# Remote_Linear_Actuator.net
KiCad netlist of a schematic drawn in Altium Designer
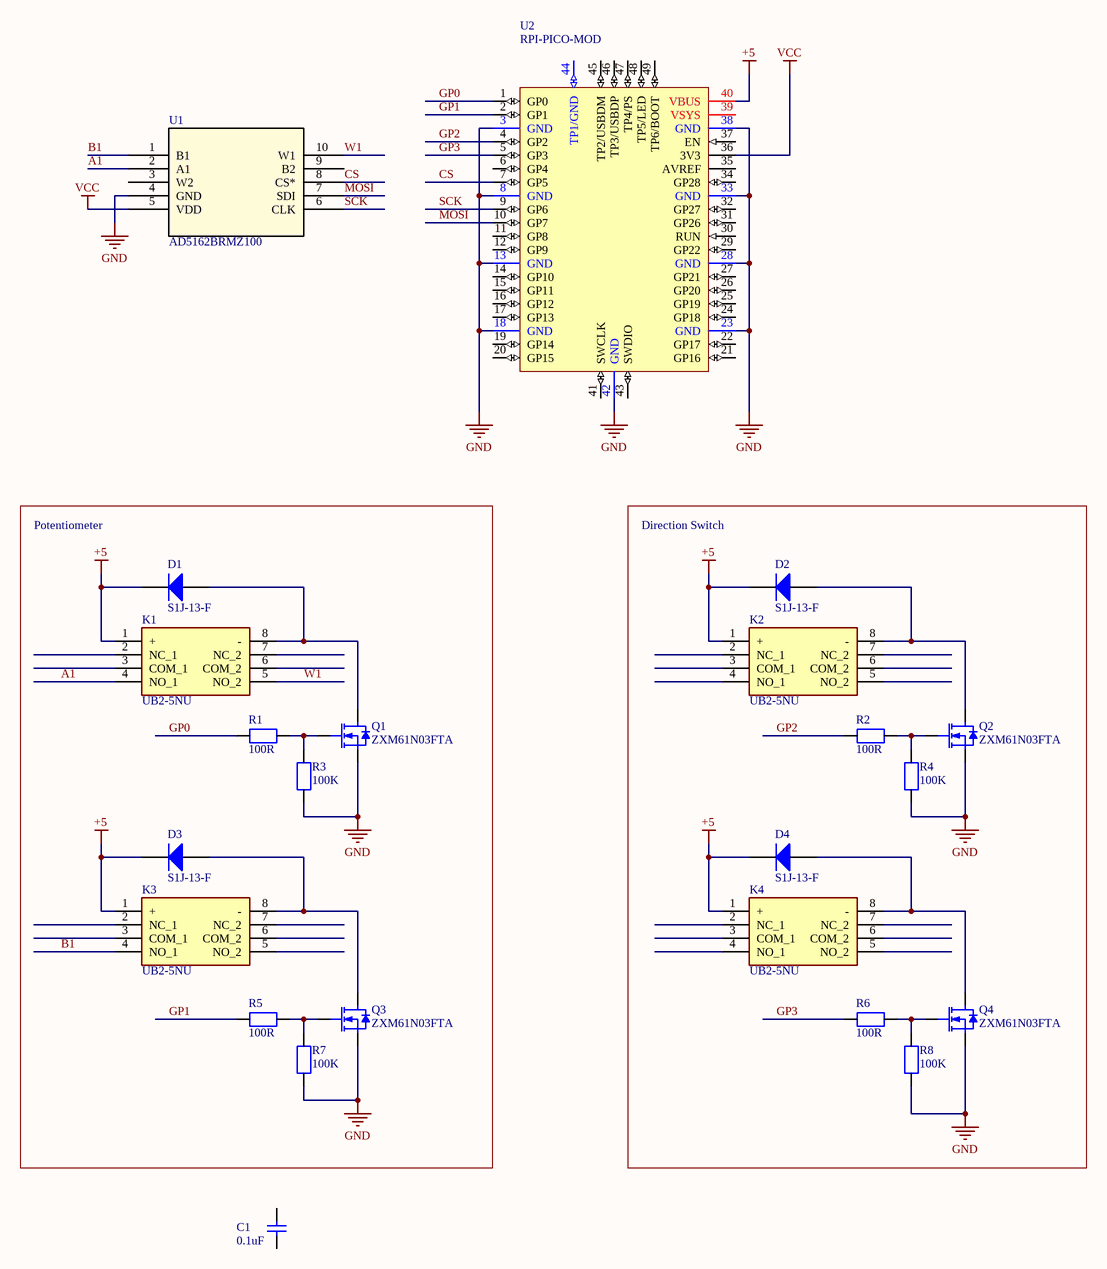
[diagram p0: Remote Linear Actuator.SchDoc]

(export (version "E")
  (design (tool "Eeschema 10.0.6"))
  (components
    (comp (ref "C1")
      (value "0.1uF")
      (footprint "0603X90")
      (description "0.1uf, 50V,0603")
      (fields (field (name "MANUFACTURER") "Yageo") (field (name "MANUFACTURERPART") "CC0603KRX7R9BB104"))
      (libsource (lib "CUSTOMSCH") (part "CAP"))
    )
    (comp (ref "D1")
      (value "S1J-13-F")
      (footprint "DIOM-430X270X245")
      (description "DIODE GEN PURP 600V 1A SMA")
      (fields (field (name "MANUFACTURER") "Diodes Incorporated"))
      (libsource (lib "CUSTOMSCH") (part "Diode"))
    )
    (comp (ref "D2")
      (value "S1J-13-F")
      (footprint "DIOM-430X270X245")
      (description "DIODE GEN PURP 600V 1A SMA")
      (fields (field (name "MANUFACTURER") "Diodes Incorporated"))
      (libsource (lib "CUSTOMSCH") (part "Diode"))
    )
    (comp (ref "D3")
      (value "S1J-13-F")
      (footprint "DIOM-430X270X245")
      (description "DIODE GEN PURP 600V 1A SMA")
      (fields (field (name "MANUFACTURER") "Diodes Incorporated"))
      (libsource (lib "CUSTOMSCH") (part "Diode"))
    )
    (comp (ref "D4")
      (value "S1J-13-F")
      (footprint "DIOM-430X270X245")
      (description "DIODE GEN PURP 600V 1A SMA")
      (fields (field (name "MANUFACTURER") "Diodes Incorporated"))
      (libsource (lib "CUSTOMSCH") (part "Diode"))
    )
    (comp (ref "K1")
      (value "UB2-5NU")
      (footprint "Siemens:UB25NU")
      (description "Relay or Contactor")
      (libsource (lib "*") (part "UB2-5NU"))
    )
    (comp (ref "K2")
      (value "UB2-5NU")
      (footprint "Siemens:UB25NU")
      (description "Relay or Contactor")
      (libsource (lib "*") (part "UB2-5NU"))
    )
    (comp (ref "K3")
      (value "UB2-5NU")
      (footprint "UB25NU")
      (description "Relay or Contactor")
      (libsource (lib "Siemens") (part "UB2-5NU"))
    )
    (comp (ref "K4")
      (value "UB2-5NU")
      (footprint "UB25NU")
      (description "Relay or Contactor")
      (libsource (lib "Siemens") (part "UB2-5NU"))
    )
    (comp (ref "Q1")
      (value "ZXM61N03FTA")
      (footprint "SOT95P240X110-3-1G-2S-3D")
      (description "30V N-CHANNEL ENHANCEMENT MODE MOSFET")
      (fields (field (name "MANUFACTURER") "Zetex"))
      (libsource (lib "CUSTOMSCH") (part "MOSFET-N"))
    )
    (comp (ref "Q2")
      (value "ZXM61N03FTA")
      (footprint "SOT95P240X110-3-1G-2S-3D")
      (description "30V N-CHANNEL ENHANCEMENT MODE MOSFET")
      (fields (field (name "MANUFACTURER") "Zetex"))
      (libsource (lib "CUSTOMSCH") (part "MOSFET-N"))
    )
    (comp (ref "Q3")
      (value "ZXM61N03FTA")
      (footprint "SOT95P240X110-3-1G-2S-3D")
      (description "30V N-CHANNEL ENHANCEMENT MODE MOSFET")
      (fields (field (name "MANUFACTURER") "Zetex"))
      (libsource (lib "CUSTOMSCH") (part "MOSFET-N"))
    )
    (comp (ref "Q4")
      (value "ZXM61N03FTA")
      (footprint "SOT95P240X110-3-1G-2S-3D")
      (description "30V N-CHANNEL ENHANCEMENT MODE MOSFET")
      (fields (field (name "MANUFACTURER") "Zetex"))
      (libsource (lib "CUSTOMSCH") (part "MOSFET-N"))
    )
    (comp (ref "R1")
      (value "100R")
      (footprint "0805X50")
      (description "100R 0805")
      (fields (field (name "MANUFACTURER") "Yageo") (field (name "MANUFACTURERPART") "RC0805FR-07150RL"))
      (libsource (lib "CUSTOMSCH") (part "RES"))
    )
    (comp (ref "R2")
      (value "100R")
      (footprint "0805X50")
      (description "100R 0805")
      (fields (field (name "MANUFACTURER") "Yageo") (field (name "MANUFACTURERPART") "RC0805FR-07150RL"))
      (libsource (lib "CUSTOMSCH") (part "RES"))
    )
    (comp (ref "R3")
      (value "100K")
      (footprint "0603X55")
      (description "RES SMD 100K OHM 1% 1/10W 0603")
      (fields (field (name "MANUFACTURER") "Yageo") (field (name "MANUFACTURERPART") "RC0603FR-07100KL"))
      (libsource (lib "") (part "RES_1"))
    )
    (comp (ref "R4")
      (value "100K")
      (footprint "0603X55")
      (description "RES SMD 100K OHM 1% 1/10W 0603")
      (fields (field (name "MANUFACTURER") "Yageo") (field (name "MANUFACTURERPART") "RC0603FR-07100KL"))
      (libsource (lib "") (part "RES_1"))
    )
    (comp (ref "R5")
      (value "100R")
      (footprint "0805X50")
      (description "100R 0805")
      (fields (field (name "MANUFACTURER") "Yageo") (field (name "MANUFACTURERPART") "RC0805FR-07150RL"))
      (libsource (lib "CUSTOMSCH") (part "RES"))
    )
    (comp (ref "R6")
      (value "100R")
      (footprint "0805X50")
      (description "100R 0805")
      (fields (field (name "MANUFACTURER") "Yageo") (field (name "MANUFACTURERPART") "RC0805FR-07150RL"))
      (libsource (lib "CUSTOMSCH") (part "RES"))
    )
    (comp (ref "R7")
      (value "100K")
      (footprint "0603X55")
      (description "RES SMD 100K OHM 1% 1/10W 0603")
      (fields (field (name "MANUFACTURER") "Yageo") (field (name "MANUFACTURERPART") "RC0603FR-07100KL"))
      (libsource (lib "") (part "RES_1"))
    )
    (comp (ref "R8")
      (value "100K")
      (footprint "0603X55")
      (description "RES SMD 100K OHM 1% 1/10W 0603")
      (fields (field (name "MANUFACTURER") "Yageo") (field (name "MANUFACTURERPART") "RC0603FR-07100KL"))
      (libsource (lib "") (part "RES_1"))
    )
    (comp (ref "U1")
      (value "AD5162BRMZ100")
      (footprint "RM_10_ADI")
      (description "No Description Available")
      (fields (field (name "COPYRIGHT") "Copyright (C) 2022 Ultra Librarian. All rights reserved."))
      (libsource (lib "AD5162BRMZ100") (part "AD5162BRMZ100"))
    )
    (comp (ref "U2")
      (value "RPI-PICO-MOD")
      (footprint "RPI-PICO-MOD")
      (description "RASPBERRY PI PICO RP2040 BOARD")
      (fields
        (field (name "MANUFACTURER") "Raspberry Pi Foundation")
        (field (name "MANUFACTURER PART NO") "SC0915")
      )
      (libsource (lib "RPi-Pico") (part "RPI-PICO-MOD"))
    )
  )
  (nets
    (net (code "1") (name "+5") (class "Default")
      (node (ref "D1") (pin "K") (pinfunction "K_K") (pintype "passive"))
      (node (ref "D2") (pin "K") (pinfunction "K_K") (pintype "passive"))
      (node (ref "D3") (pin "K") (pinfunction "K_K") (pintype "passive"))
      (node (ref "D4") (pin "K") (pinfunction "K_K") (pintype "passive"))
      (node (ref "K1") (pin "1") (pinfunction "+_1") (pintype "passive"))
      (node (ref "K2") (pin "1") (pinfunction "+_1") (pintype "passive"))
      (node (ref "K3") (pin "1") (pinfunction "+_1") (pintype "passive"))
      (node (ref "K4") (pin "1") (pinfunction "+_1") (pintype "passive"))
      (node (ref "U2") (pin "40") (pinfunction "VBUS_40") (pintype "power_in"))
    )
    (net (code "2") (name "/A1") (class "Default")
      (node (ref "K1") (pin "4") (pinfunction "NO_1_4") (pintype "passive"))
      (node (ref "U1") (pin "2") (pinfunction "A1_2") (pintype "passive"))
    )
    (net (code "3") (name "/B1") (class "Default")
      (node (ref "K3") (pin "4") (pinfunction "NO_1_4") (pintype "passive"))
      (node (ref "U1") (pin "1") (pinfunction "B1_1") (pintype "passive"))
    )
    (net (code "4") (name "/CS") (class "Default")
      (node (ref "U1") (pin "8") (pinfunction "CS*_8") (pintype "passive"))
      (node (ref "U2") (pin "7") (pinfunction "GP5_7") (pintype "bidirectional"))
    )
    (net (code "5") (name "/GP0") (class "Default")
      (node (ref "R1") (pin "2") (pinfunction "2_2") (pintype "passive"))
      (node (ref "U2") (pin "1") (pinfunction "GP0_1") (pintype "bidirectional"))
    )
    (net (code "6") (name "/GP1") (class "Default")
      (node (ref "R5") (pin "2") (pinfunction "2_2") (pintype "passive"))
      (node (ref "U2") (pin "2") (pinfunction "GP1_2") (pintype "bidirectional"))
    )
    (net (code "7") (name "/GP2") (class "Default")
      (node (ref "R2") (pin "2") (pinfunction "2_2") (pintype "passive"))
      (node (ref "U2") (pin "4") (pinfunction "GP2_4") (pintype "bidirectional"))
    )
    (net (code "8") (name "/GP3") (class "Default")
      (node (ref "R6") (pin "2") (pinfunction "2_2") (pintype "passive"))
      (node (ref "U2") (pin "5") (pinfunction "GP3_5") (pintype "bidirectional"))
    )
    (net (code "9") (name "/MOSI") (class "Default")
      (node (ref "U1") (pin "7") (pinfunction "SDI_7") (pintype "passive"))
      (node (ref "U2") (pin "10") (pinfunction "GP7_10") (pintype "bidirectional"))
    )
    (net (code "10") (name "/SCK") (class "Default")
      (node (ref "U1") (pin "6") (pinfunction "CLK_6") (pintype "passive"))
      (node (ref "U2") (pin "9") (pinfunction "GP6_9") (pintype "bidirectional"))
    )
    (net (code "11") (name "/W1") (class "Default")
      (node (ref "K1") (pin "5") (pinfunction "NO_2_5") (pintype "passive"))
      (node (ref "U1") (pin "10") (pinfunction "W1_10") (pintype "passive"))
    )
    (net (code "12") (name "GND") (class "Default")
      (node (ref "Q1") (pin "S") (pinfunction "S_S") (pintype "passive"))
      (node (ref "Q2") (pin "S") (pinfunction "S_S") (pintype "passive"))
      (node (ref "Q3") (pin "S") (pinfunction "S_S") (pintype "passive"))
      (node (ref "Q4") (pin "S") (pinfunction "S_S") (pintype "passive"))
      (node (ref "R3") (pin "2") (pinfunction "2_2") (pintype "passive"))
      (node (ref "R4") (pin "2") (pinfunction "2_2") (pintype "passive"))
      (node (ref "R7") (pin "2") (pinfunction "2_2") (pintype "passive"))
      (node (ref "R8") (pin "2") (pinfunction "2_2") (pintype "passive"))
      (node (ref "U1") (pin "4") (pinfunction "GND_4") (pintype "passive"))
      (node (ref "U2") (pin "13") (pinfunction "GND_13") (pintype "power_in"))
      (node (ref "U2") (pin "18") (pinfunction "GND_18") (pintype "power_in"))
      (node (ref "U2") (pin "23") (pinfunction "GND_23") (pintype "power_in"))
      (node (ref "U2") (pin "28") (pinfunction "GND_28") (pintype "power_in"))
      (node (ref "U2") (pin "3") (pinfunction "GND_3") (pintype "power_in"))
      (node (ref "U2") (pin "33") (pinfunction "GND_33") (pintype "power_in"))
      (node (ref "U2") (pin "38") (pinfunction "GND_38") (pintype "power_in"))
      (node (ref "U2") (pin "42") (pinfunction "GND_42") (pintype "power_in"))
      (node (ref "U2") (pin "8") (pinfunction "GND_8") (pintype "power_in"))
    )
    (net (code "13") (name "Net-(K1--)") (class "Default")
      (node (ref "D1") (pin "A") (pinfunction "A_A") (pintype "passive"))
      (node (ref "K1") (pin "8") (pinfunction "-_8") (pintype "passive"))
      (node (ref "Q1") (pin "D") (pinfunction "D_D") (pintype "passive"))
    )
    (net (code "14") (name "Net-(K2--)") (class "Default")
      (node (ref "D2") (pin "A") (pinfunction "A_A") (pintype "passive"))
      (node (ref "K2") (pin "8") (pinfunction "-_8") (pintype "passive"))
      (node (ref "Q2") (pin "D") (pinfunction "D_D") (pintype "passive"))
    )
    (net (code "15") (name "Net-(K3--)") (class "Default")
      (node (ref "D3") (pin "A") (pinfunction "A_A") (pintype "passive"))
      (node (ref "K3") (pin "8") (pinfunction "-_8") (pintype "passive"))
      (node (ref "Q3") (pin "D") (pinfunction "D_D") (pintype "passive"))
    )
    (net (code "16") (name "Net-(K4--)") (class "Default")
      (node (ref "D4") (pin "A") (pinfunction "A_A") (pintype "passive"))
      (node (ref "K4") (pin "8") (pinfunction "-_8") (pintype "passive"))
      (node (ref "Q4") (pin "D") (pinfunction "D_D") (pintype "passive"))
    )
    (net (code "17") (name "Net-(Q1-PadG)") (class "Default")
      (node (ref "Q1") (pin "G") (pinfunction "G_G") (pintype "passive"))
      (node (ref "R1") (pin "1") (pinfunction "1_1") (pintype "passive"))
      (node (ref "R3") (pin "1") (pinfunction "1_1") (pintype "passive"))
    )
    (net (code "18") (name "Net-(Q2-PadG)") (class "Default")
      (node (ref "Q2") (pin "G") (pinfunction "G_G") (pintype "passive"))
      (node (ref "R2") (pin "1") (pinfunction "1_1") (pintype "passive"))
      (node (ref "R4") (pin "1") (pinfunction "1_1") (pintype "passive"))
    )
    (net (code "19") (name "Net-(Q3-PadG)") (class "Default")
      (node (ref "Q3") (pin "G") (pinfunction "G_G") (pintype "passive"))
      (node (ref "R5") (pin "1") (pinfunction "1_1") (pintype "passive"))
      (node (ref "R7") (pin "1") (pinfunction "1_1") (pintype "passive"))
    )
    (net (code "20") (name "Net-(Q4-PadG)") (class "Default")
      (node (ref "Q4") (pin "G") (pinfunction "G_G") (pintype "passive"))
      (node (ref "R6") (pin "1") (pinfunction "1_1") (pintype "passive"))
      (node (ref "R8") (pin "1") (pinfunction "1_1") (pintype "passive"))
    )
    (net (code "21") (name "VCC") (class "Default")
      (node (ref "U1") (pin "5") (pinfunction "VDD_5") (pintype "power_in"))
      (node (ref "U2") (pin "36") (pinfunction "3V3_36") (pintype "power_in"))
    )
    (net (code "22") (name "unconnected-(C1-Pad1)") (class "Default")
      (node (ref "C1") (pin "1") (pinfunction "1_1") (pintype "passive"))
    )
    (net (code "23") (name "unconnected-(C1-Pad2)") (class "Default")
      (node (ref "C1") (pin "2") (pinfunction "2_2") (pintype "passive"))
    )
    (net (code "24") (name "unconnected-(K1-COM_1-Pad3)") (class "Default")
      (node (ref "K1") (pin "3") (pinfunction "COM_1_3") (pintype "passive"))
    )
    (net (code "25") (name "unconnected-(K1-COM_2-Pad6)") (class "Default")
      (node (ref "K1") (pin "6") (pinfunction "COM_2_6") (pintype "passive"))
    )
    (net (code "26") (name "unconnected-(K1-NC_1-Pad2)") (class "Default")
      (node (ref "K1") (pin "2") (pinfunction "NC_1_2") (pintype "passive"))
    )
    (net (code "27") (name "unconnected-(K1-NC_2-Pad7)") (class "Default")
      (node (ref "K1") (pin "7") (pinfunction "NC_2_7") (pintype "passive"))
    )
    (net (code "28") (name "unconnected-(K2-COM_1-Pad3)") (class "Default")
      (node (ref "K2") (pin "3") (pinfunction "COM_1_3") (pintype "passive"))
    )
    (net (code "29") (name "unconnected-(K2-COM_2-Pad6)") (class "Default")
      (node (ref "K2") (pin "6") (pinfunction "COM_2_6") (pintype "passive"))
    )
    (net (code "30") (name "unconnected-(K2-NC_1-Pad2)") (class "Default")
      (node (ref "K2") (pin "2") (pinfunction "NC_1_2") (pintype "passive"))
    )
    (net (code "31") (name "unconnected-(K2-NC_2-Pad7)") (class "Default")
      (node (ref "K2") (pin "7") (pinfunction "NC_2_7") (pintype "passive"))
    )
    (net (code "32") (name "unconnected-(K2-NO_1-Pad4)") (class "Default")
      (node (ref "K2") (pin "4") (pinfunction "NO_1_4") (pintype "passive"))
    )
    (net (code "33") (name "unconnected-(K2-NO_2-Pad5)") (class "Default")
      (node (ref "K2") (pin "5") (pinfunction "NO_2_5") (pintype "passive"))
    )
    (net (code "34") (name "unconnected-(K3-COM_1-Pad3)") (class "Default")
      (node (ref "K3") (pin "3") (pinfunction "COM_1_3") (pintype "passive"))
    )
    (net (code "35") (name "unconnected-(K3-COM_2-Pad6)") (class "Default")
      (node (ref "K3") (pin "6") (pinfunction "COM_2_6") (pintype "passive"))
    )
    (net (code "36") (name "unconnected-(K3-NC_1-Pad2)") (class "Default")
      (node (ref "K3") (pin "2") (pinfunction "NC_1_2") (pintype "passive"))
    )
    (net (code "37") (name "unconnected-(K3-NC_2-Pad7)") (class "Default")
      (node (ref "K3") (pin "7") (pinfunction "NC_2_7") (pintype "passive"))
    )
    (net (code "38") (name "unconnected-(K3-NO_2-Pad5)") (class "Default")
      (node (ref "K3") (pin "5") (pinfunction "NO_2_5") (pintype "passive"))
    )
    (net (code "39") (name "unconnected-(K4-COM_1-Pad3)") (class "Default")
      (node (ref "K4") (pin "3") (pinfunction "COM_1_3") (pintype "passive"))
    )
    (net (code "40") (name "unconnected-(K4-COM_2-Pad6)") (class "Default")
      (node (ref "K4") (pin "6") (pinfunction "COM_2_6") (pintype "passive"))
    )
    (net (code "41") (name "unconnected-(K4-NC_1-Pad2)") (class "Default")
      (node (ref "K4") (pin "2") (pinfunction "NC_1_2") (pintype "passive"))
    )
    (net (code "42") (name "unconnected-(K4-NC_2-Pad7)") (class "Default")
      (node (ref "K4") (pin "7") (pinfunction "NC_2_7") (pintype "passive"))
    )
    (net (code "43") (name "unconnected-(K4-NO_1-Pad4)") (class "Default")
      (node (ref "K4") (pin "4") (pinfunction "NO_1_4") (pintype "passive"))
    )
    (net (code "44") (name "unconnected-(K4-NO_2-Pad5)") (class "Default")
      (node (ref "K4") (pin "5") (pinfunction "NO_2_5") (pintype "passive"))
    )
    (net (code "45") (name "unconnected-(U1-B2-Pad9)") (class "Default")
      (node (ref "U1") (pin "9") (pinfunction "B2_9") (pintype "passive"))
    )
    (net (code "46") (name "unconnected-(U1-W2-Pad3)") (class "Default")
      (node (ref "U1") (pin "3") (pinfunction "W2_3") (pintype "passive"))
    )
    (net (code "47") (name "unconnected-(U2-AVREF-Pad35)") (class "Default")
      (node (ref "U2") (pin "35") (pinfunction "AVREF_35") (pintype "power_in"))
    )
    (net (code "48") (name "unconnected-(U2-EN-Pad37)") (class "Default")
      (node (ref "U2") (pin "37") (pinfunction "EN_37") (pintype "input"))
    )
    (net (code "49") (name "unconnected-(U2-GP4-Pad6)") (class "Default")
      (node (ref "U2") (pin "6") (pinfunction "GP4_6") (pintype "bidirectional"))
    )
    (net (code "50") (name "unconnected-(U2-GP8-Pad11)") (class "Default")
      (node (ref "U2") (pin "11") (pinfunction "GP8_11") (pintype "bidirectional"))
    )
    (net (code "51") (name "unconnected-(U2-GP9-Pad12)") (class "Default")
      (node (ref "U2") (pin "12") (pinfunction "GP9_12") (pintype "bidirectional"))
    )
    (net (code "52") (name "unconnected-(U2-GP10-Pad14)") (class "Default")
      (node (ref "U2") (pin "14") (pinfunction "GP10_14") (pintype "bidirectional"))
    )
    (net (code "53") (name "unconnected-(U2-GP11-Pad15)") (class "Default")
      (node (ref "U2") (pin "15") (pinfunction "GP11_15") (pintype "bidirectional"))
    )
    (net (code "54") (name "unconnected-(U2-GP12-Pad16)") (class "Default")
      (node (ref "U2") (pin "16") (pinfunction "GP12_16") (pintype "bidirectional"))
    )
    (net (code "55") (name "unconnected-(U2-GP13-Pad17)") (class "Default")
      (node (ref "U2") (pin "17") (pinfunction "GP13_17") (pintype "bidirectional"))
    )
    (net (code "56") (name "unconnected-(U2-GP14-Pad19)") (class "Default")
      (node (ref "U2") (pin "19") (pinfunction "GP14_19") (pintype "bidirectional"))
    )
    (net (code "57") (name "unconnected-(U2-GP15-Pad20)") (class "Default")
      (node (ref "U2") (pin "20") (pinfunction "GP15_20") (pintype "bidirectional"))
    )
    (net (code "58") (name "unconnected-(U2-GP16-Pad21)") (class "Default")
      (node (ref "U2") (pin "21") (pinfunction "GP16_21") (pintype "bidirectional"))
    )
    (net (code "59") (name "unconnected-(U2-GP17-Pad22)") (class "Default")
      (node (ref "U2") (pin "22") (pinfunction "GP17_22") (pintype "bidirectional"))
    )
    (net (code "60") (name "unconnected-(U2-GP18-Pad24)") (class "Default")
      (node (ref "U2") (pin "24") (pinfunction "GP18_24") (pintype "bidirectional"))
    )
    (net (code "61") (name "unconnected-(U2-GP19-Pad25)") (class "Default")
      (node (ref "U2") (pin "25") (pinfunction "GP19_25") (pintype "bidirectional"))
    )
    (net (code "62") (name "unconnected-(U2-GP20-Pad26)") (class "Default")
      (node (ref "U2") (pin "26") (pinfunction "GP20_26") (pintype "bidirectional"))
    )
    (net (code "63") (name "unconnected-(U2-GP21-Pad27)") (class "Default")
      (node (ref "U2") (pin "27") (pinfunction "GP21_27") (pintype "bidirectional"))
    )
    (net (code "64") (name "unconnected-(U2-GP22-Pad29)") (class "Default")
      (node (ref "U2") (pin "29") (pinfunction "GP22_29") (pintype "bidirectional"))
    )
    (net (code "65") (name "unconnected-(U2-GP26-Pad31)") (class "Default")
      (node (ref "U2") (pin "31") (pinfunction "GP26_31") (pintype "bidirectional"))
    )
    (net (code "66") (name "unconnected-(U2-GP27-Pad32)") (class "Default")
      (node (ref "U2") (pin "32") (pinfunction "GP27_32") (pintype "bidirectional"))
    )
    (net (code "67") (name "unconnected-(U2-GP28-Pad34)") (class "Default")
      (node (ref "U2") (pin "34") (pinfunction "GP28_34") (pintype "bidirectional"))
    )
    (net (code "68") (name "unconnected-(U2-RUN-Pad30)") (class "Default")
      (node (ref "U2") (pin "30") (pinfunction "RUN_30") (pintype "input"))
    )
    (net (code "69") (name "unconnected-(U2-SWCLK-Pad41)") (class "Default")
      (node (ref "U2") (pin "41") (pinfunction "SWCLK_41") (pintype "bidirectional"))
    )
    (net (code "70") (name "unconnected-(U2-SWDIO-Pad43)") (class "Default")
      (node (ref "U2") (pin "43") (pinfunction "SWDIO_43") (pintype "bidirectional"))
    )
    (net (code "71") (name "unconnected-(U2-TP1{slash}GND-Pad44)") (class "Default")
      (node (ref "U2") (pin "44") (pinfunction "TP1/GND_44") (pintype "bidirectional"))
    )
    (net (code "72") (name "unconnected-(U2-TP2{slash}USBDM-Pad45)") (class "Default")
      (node (ref "U2") (pin "45") (pinfunction "TP2/USBDM_45") (pintype "bidirectional"))
    )
    (net (code "73") (name "unconnected-(U2-TP3{slash}USBDP-Pad46)") (class "Default")
      (node (ref "U2") (pin "46") (pinfunction "TP3/USBDP_46") (pintype "bidirectional"))
    )
    (net (code "74") (name "unconnected-(U2-TP4{slash}PS-Pad47)") (class "Default")
      (node (ref "U2") (pin "47") (pinfunction "TP4/PS_47") (pintype "bidirectional"))
    )
    (net (code "75") (name "unconnected-(U2-TP5{slash}LED-Pad48)") (class "Default")
      (node (ref "U2") (pin "48") (pinfunction "TP5/LED_48") (pintype "bidirectional"))
    )
    (net (code "76") (name "unconnected-(U2-TP6{slash}BOOT-Pad49)") (class "Default")
      (node (ref "U2") (pin "49") (pinfunction "TP6/BOOT_49") (pintype "bidirectional"))
    )
    (net (code "77") (name "unconnected-(U2-VSYS-Pad39)") (class "Default")
      (node (ref "U2") (pin "39") (pinfunction "VSYS_39") (pintype "power_in"))
    )
  )
)
